# Front_DisplayKey.net
KiCad netlist of a schematic drawn in Altium Designer
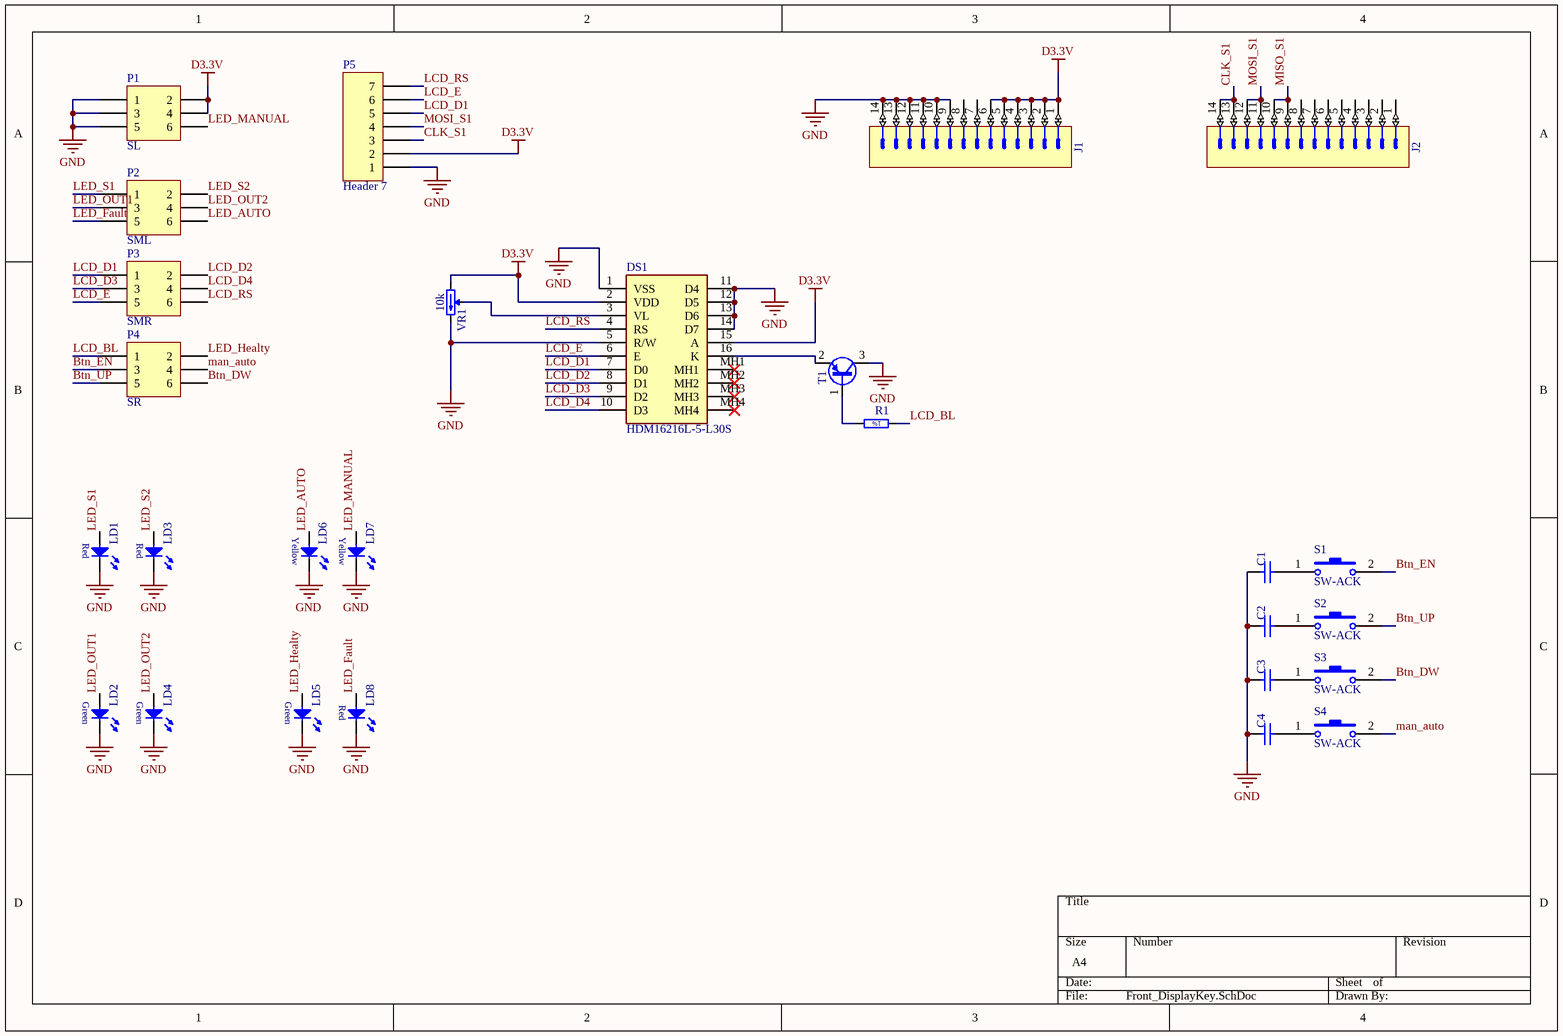
[diagram p0: Front_DisplayKey.SchDoc]

(export (version "E")
  (design (tool "Eeschema 10.0.6"))
  (components
    (comp (ref "C1")
      (value "0.1uf")
      (footprint "CAPC2012X135N")
      (description "0092-0004-8")
      (fields
        (field (name "PART NUMBER") "CC0805_100NF_50V_10%_X7R")
        (field (name "VOLTAGE") "50V")
        (field (name "AUTHOR") "CERN DEM JLC")
      )
      (libsource (lib "Capacitors") (part "Capacitor - non polarized"))
    )
    (comp (ref "C2")
      (value "0.1uf")
      (footprint "CAPC2012X135N")
      (description "0092-0004-8")
      (fields
        (field (name "PART NUMBER") "CC0805_100NF_50V_10%_X7R")
        (field (name "VOLTAGE") "50V")
        (field (name "AUTHOR") "CERN DEM JLC")
      )
      (libsource (lib "Capacitors") (part "Capacitor - non polarized"))
    )
    (comp (ref "C3")
      (value "0.1uf")
      (footprint "CAPC2012X135N")
      (description "0092-0004-8")
      (fields
        (field (name "PART NUMBER") "CC0805_100NF_50V_10%_X7R")
        (field (name "VOLTAGE") "50V")
        (field (name "AUTHOR") "CERN DEM JLC")
      )
      (libsource (lib "Capacitors") (part "Capacitor - non polarized"))
    )
    (comp (ref "C4")
      (value "0.1uf")
      (footprint "CAPC2012X135N")
      (description "0092-0004-8")
      (fields
        (field (name "PART NUMBER") "CC0805_100NF_50V_10%_X7R")
        (field (name "VOLTAGE") "50V")
        (field (name "AUTHOR") "CERN DEM JLC")
      )
      (libsource (lib "Capacitors") (part "Capacitor - non polarized"))
    )
    (comp (ref "DS1")
      (value "HDM16216L-5-L30S")
      (footprint "SamacSys:HDM16216L5L30S")
      (description "Display")
      (libsource (lib "*") (part "HDM16216L-5-L30S"))
    )
    (comp (ref "J1")
      (value "Header 14")
      (footprint "STELVIO-KONTEK_3910401114400")
      (description "Connector 14 Male")
      (fields
        (field (name "PART NUMBER") "STELVIO-KONTEK_3910401114400")
        (field (name "MANUFACTURER") "STELVIO-KONTEK")
        (field (name "AUTHOR") "CERN DEM JLC")
      )
      (libsource (lib "Connectors") (part "Connector 14 Male"))
    )
    (comp (ref "J2")
      (value "Header 14")
      (footprint "STELVIO-KONTEK_3910401114400")
      (description "Connector 14 Male")
      (fields
        (field (name "PART NUMBER") "STELVIO-KONTEK_3910401114400")
        (field (name "MANUFACTURER") "STELVIO-KONTEK")
        (field (name "AUTHOR") "CERN DEM JLC")
      )
      (libsource (lib "Connectors") (part "Connector 14 Male"))
    )
    (comp (ref "LD1")
      (value "Red")
      (footprint "LED_5MM_RED_1C-2A")
      (description "LED Red 1C 2A")
      (fields
        (field (name "PART NUMBER") "LED_AVAGO_HLMP-3301")
        (field (name "MANUFACTURER") "AVAGO TECHNOLOGIES")
        (field (name "AUTHOR") "CERN DEM JLC")
      )
      (libsource (lib "ICs And Semiconductors") (part "LED Red 1C 2A"))
    )
    (comp (ref "LD2")
      (value "Green")
      (footprint "LED_3MM_GREEN_1C-2A")
      (description "LED Green 1C 2A")
      (fields
        (field (name "PART NUMBER") "LED_AVAGO_HLMP-1790")
        (field (name "MANUFACTURER") "AVAGO TECHNOLOGIES")
        (field (name "AUTHOR") "CERN DEM JLC")
      )
      (libsource (lib "ICs And Semiconductors") (part "LED Green 1C 2A"))
    )
    (comp (ref "LD3")
      (value "Red")
      (footprint "LED_5MM_RED_1C-2A")
      (description "LED Red 1C 2A")
      (fields
        (field (name "PART NUMBER") "LED_AVAGO_HLMP-3301")
        (field (name "MANUFACTURER") "AVAGO TECHNOLOGIES")
        (field (name "AUTHOR") "CERN DEM JLC")
      )
      (libsource (lib "ICs And Semiconductors") (part "LED Red 1C 2A"))
    )
    (comp (ref "LD4")
      (value "Green")
      (footprint "LED_3MM_GREEN_1C-2A")
      (description "LED Green 1C 2A")
      (fields
        (field (name "PART NUMBER") "LED_AVAGO_HLMP-1790")
        (field (name "MANUFACTURER") "AVAGO TECHNOLOGIES")
        (field (name "AUTHOR") "CERN DEM JLC")
      )
      (libsource (lib "ICs And Semiconductors") (part "LED Green 1C 2A"))
    )
    (comp (ref "LD5")
      (value "Green")
      (footprint "LED_3MM_GREEN_1C-2A")
      (description "LED Green 1C 2A")
      (fields
        (field (name "PART NUMBER") "LED_AVAGO_HLMP-1790")
        (field (name "MANUFACTURER") "AVAGO TECHNOLOGIES")
        (field (name "AUTHOR") "CERN DEM JLC")
      )
      (libsource (lib "ICs And Semiconductors") (part "LED Green 1C 2A"))
    )
    (comp (ref "LD6")
      (value "Yellow")
      (footprint "LED_3MM_YELLOW_1C-2A")
      (description "LED Yellow 1C 2A")
      (fields
        (field (name "PART NUMBER") "LED_AVAGO_HLMP-1719")
        (field (name "MANUFACTURER") "AVAGO TECHNOLOGIES")
        (field (name "AUTHOR") "CERN DEM JLC")
      )
      (libsource (lib "ICs And Semiconductors") (part "LED Yellow 1C 2A"))
    )
    (comp (ref "LD7")
      (value "Yellow")
      (footprint "LED_3MM_YELLOW_1C-2A")
      (description "LED Yellow 1C 2A")
      (fields
        (field (name "PART NUMBER") "LED_AVAGO_HLMP-1719")
        (field (name "MANUFACTURER") "AVAGO TECHNOLOGIES")
        (field (name "AUTHOR") "CERN DEM JLC")
      )
      (libsource (lib "ICs And Semiconductors") (part "LED Yellow 1C 2A"))
    )
    (comp (ref "LD8")
      (value "Red")
      (footprint "LED_5MM_RED_1C-2A")
      (description "LED Red 1C 2A")
      (fields
        (field (name "PART NUMBER") "LED_AVAGO_HLMP-3301")
        (field (name "MANUFACTURER") "AVAGO TECHNOLOGIES")
        (field (name "AUTHOR") "CERN DEM JLC")
      )
      (libsource (lib "ICs And Semiconductors") (part "LED Red 1C 2A"))
    )
    (comp (ref "P1")
      (value "SL")
      (footprint "HDR2X3")
      (description "Header, 3-Pin, Dual row")
      (fields (field (name "PUBLISHER") "Altium Limited"))
      (libsource (lib "Miscellaneous Connectors") (part "Header 3X2"))
    )
    (comp (ref "P2")
      (value "SML")
      (footprint "HDR2X3")
      (description "Header, 3-Pin, Dual row")
      (fields (field (name "PUBLISHER") "Altium Limited"))
      (libsource (lib "Miscellaneous Connectors") (part "Header 3X2"))
    )
    (comp (ref "P3")
      (value "SMR")
      (footprint "HDR2X3")
      (description "Header, 3-Pin, Dual row")
      (fields (field (name "PUBLISHER") "Altium Limited"))
      (libsource (lib "Miscellaneous Connectors") (part "Header 3X2"))
    )
    (comp (ref "P4")
      (value "SR")
      (footprint "HDR2X3")
      (description "Header, 3-Pin, Dual row")
      (fields (field (name "PUBLISHER") "Altium Limited"))
      (libsource (lib "Miscellaneous Connectors") (part "Header 3X2"))
    )
    (comp (ref "P5")
      (value "Header 7")
      (footprint "HDR1X7")
      (description "Header, 7-Pin")
      (fields (field (name "PUBLISHER") "Altium Limited"))
      (libsource (lib "Miscellaneous Connectors") (part "Header 7"))
    )
    (comp (ref "R1")
      (value "1k")
      (footprint "RESC2012X60N")
      (description "Resistor - 1%")
      (fields
        (field (name "PART NUMBER") "R0805_1K_1%_0.125W_100PPM")
        (field (name "POWER") "0.125W")
        (field (name "AUTHOR") "CERN DEM JLC")
      )
      (libsource (lib "Resistors") (part "Resistor - 1%"))
    )
    (comp (ref "S1")
      (value "SW-ACK")
      (footprint "SW_PB1")
      (description "Switch")
      (fields (field (name "PUBLISHER") "Altium Limited"))
      (libsource (lib "Miscellaneous Devices") (part "SW-PB"))
    )
    (comp (ref "S2")
      (value "SW-ACK")
      (footprint "SW_PB1")
      (description "Switch")
      (fields (field (name "PUBLISHER") "Altium Limited"))
      (libsource (lib "Miscellaneous Devices") (part "SW-PB"))
    )
    (comp (ref "S3")
      (value "SW-ACK")
      (footprint "SW_PB1")
      (description "Switch")
      (fields (field (name "PUBLISHER") "Altium Limited"))
      (libsource (lib "Miscellaneous Devices") (part "SW-PB"))
    )
    (comp (ref "S4")
      (value "SW-ACK")
      (footprint "SW_PB1")
      (description "Switch")
      (fields (field (name "PUBLISHER") "Altium Limited"))
      (libsource (lib "Miscellaneous Devices") (part "SW-PB"))
    )
    (comp (ref "T1")
      (value "MMBT3906LT1G")
      (footprint "SOT95P240X110-3N")
      (description "0235-0223-4")
      (fields
        (field (name "PART NUMBER") "BSR18A")
        (field (name "MANUFACTURER") "FAIRCHILD SEMICONDUCTOR")
        (field (name "AUTHOR") "CERN DEM JLC")
      )
      (libsource (lib "ICs And Semiconductors") (part "PNP B1 E2 C3"))
    )
    (comp (ref "VR1")
      (value "10k")
      (footprint "VR5")
      (description "0141-0259-5")
      (fields
        (field (name "PART NUMBER") "TRIM_12T_100K_BOURNS_3266W-1-104LF")
        (field (name "POWER") "0.25W")
        (field (name "AUTHOR") "CERN DEM JLC")
      )
      (libsource (lib "Resistors") (part "Trimming Potentiometer"))
    )
  )
  (nets
    (net (code "1") (name "/Btn_DW") (class "Default")
      (node (ref "P4") (pin "6") (pinfunction "6_6") (pintype "passive"))
      (node (ref "S3") (pin "2") (pinfunction "2_2") (pintype "passive"))
    )
    (net (code "2") (name "/Btn_EN") (class "Default")
      (node (ref "P4") (pin "3") (pinfunction "3_3") (pintype "passive"))
      (node (ref "S1") (pin "2") (pinfunction "2_2") (pintype "passive"))
    )
    (net (code "3") (name "/Btn_UP") (class "Default")
      (node (ref "P4") (pin "5") (pinfunction "5_5") (pintype "passive"))
      (node (ref "S2") (pin "2") (pinfunction "2_2") (pintype "passive"))
    )
    (net (code "4") (name "/CLK_S1") (class "Default")
      (node (ref "J2") (pin "13") (pinfunction "13_13") (pintype "bidirectional"))
      (node (ref "J2") (pin "14") (pinfunction "14_14") (pintype "bidirectional"))
      (node (ref "P5") (pin "3") (pinfunction "3_3") (pintype "passive"))
    )
    (net (code "5") (name "/LCD_BL") (class "Default")
      (node (ref "P4") (pin "1") (pinfunction "1_1") (pintype "passive"))
      (node (ref "R1") (pin "1") (pinfunction "1_1") (pintype "passive"))
    )
    (net (code "6") (name "/LCD_D1") (class "Default")
      (node (ref "DS1") (pin "7") (pinfunction "D0_7") (pintype "passive"))
      (node (ref "P3") (pin "1") (pinfunction "1_1") (pintype "passive"))
      (node (ref "P5") (pin "5") (pinfunction "5_5") (pintype "passive"))
    )
    (net (code "7") (name "/LCD_D2") (class "Default")
      (node (ref "DS1") (pin "8") (pinfunction "D1_8") (pintype "passive"))
      (node (ref "P3") (pin "2") (pinfunction "2_2") (pintype "passive"))
    )
    (net (code "8") (name "/LCD_D3") (class "Default")
      (node (ref "DS1") (pin "9") (pinfunction "D2_9") (pintype "passive"))
      (node (ref "P3") (pin "3") (pinfunction "3_3") (pintype "passive"))
    )
    (net (code "9") (name "/LCD_D4") (class "Default")
      (node (ref "DS1") (pin "10") (pinfunction "D3_10") (pintype "passive"))
      (node (ref "P3") (pin "4") (pinfunction "4_4") (pintype "passive"))
    )
    (net (code "10") (name "/LCD_E") (class "Default")
      (node (ref "DS1") (pin "6") (pinfunction "E_6") (pintype "passive"))
      (node (ref "P3") (pin "5") (pinfunction "5_5") (pintype "passive"))
      (node (ref "P5") (pin "6") (pinfunction "6_6") (pintype "passive"))
    )
    (net (code "11") (name "/LCD_RS") (class "Default")
      (node (ref "DS1") (pin "4") (pinfunction "RS_4") (pintype "passive"))
      (node (ref "P3") (pin "6") (pinfunction "6_6") (pintype "passive"))
      (node (ref "P5") (pin "7") (pinfunction "7_7") (pintype "passive"))
    )
    (net (code "12") (name "/LED_AUTO") (class "Default")
      (node (ref "LD6") (pin "2") (pinfunction "A_2") (pintype "passive"))
      (node (ref "P2") (pin "6") (pinfunction "6_6") (pintype "passive"))
    )
    (net (code "13") (name "/LED_Fault") (class "Default")
      (node (ref "LD8") (pin "2") (pinfunction "A_2") (pintype "passive"))
      (node (ref "P2") (pin "5") (pinfunction "5_5") (pintype "passive"))
    )
    (net (code "14") (name "/LED_Healty") (class "Default")
      (node (ref "LD5") (pin "2") (pinfunction "A_2") (pintype "passive"))
      (node (ref "P4") (pin "2") (pinfunction "2_2") (pintype "passive"))
    )
    (net (code "15") (name "/LED_MANUAL") (class "Default")
      (node (ref "LD7") (pin "2") (pinfunction "A_2") (pintype "passive"))
      (node (ref "P1") (pin "6") (pinfunction "6_6") (pintype "passive"))
    )
    (net (code "16") (name "/LED_OUT1") (class "Default")
      (node (ref "LD2") (pin "2") (pinfunction "A_2") (pintype "passive"))
      (node (ref "P2") (pin "3") (pinfunction "3_3") (pintype "passive"))
    )
    (net (code "17") (name "/LED_OUT2") (class "Default")
      (node (ref "LD4") (pin "2") (pinfunction "A_2") (pintype "passive"))
      (node (ref "P2") (pin "4") (pinfunction "4_4") (pintype "passive"))
    )
    (net (code "18") (name "/LED_S1") (class "Default")
      (node (ref "LD1") (pin "2") (pinfunction "A_2") (pintype "passive"))
      (node (ref "P2") (pin "1") (pinfunction "1_1") (pintype "passive"))
    )
    (net (code "19") (name "/LED_S2") (class "Default")
      (node (ref "LD3") (pin "2") (pinfunction "A_2") (pintype "passive"))
      (node (ref "P2") (pin "2") (pinfunction "2_2") (pintype "passive"))
    )
    (net (code "20") (name "/MISO_S1") (class "Default")
      (node (ref "J2") (pin "10") (pinfunction "10_10") (pintype "bidirectional"))
      (node (ref "J2") (pin "9") (pinfunction "9_9") (pintype "bidirectional"))
    )
    (net (code "21") (name "/MOSI_S1") (class "Default")
      (node (ref "J2") (pin "11") (pinfunction "11_11") (pintype "bidirectional"))
      (node (ref "J2") (pin "12") (pinfunction "12_12") (pintype "bidirectional"))
      (node (ref "P5") (pin "4") (pinfunction "4_4") (pintype "passive"))
    )
    (net (code "22") (name "/man_auto") (class "Default")
      (node (ref "P4") (pin "4") (pinfunction "4_4") (pintype "passive"))
      (node (ref "S4") (pin "2") (pinfunction "2_2") (pintype "passive"))
    )
    (net (code "23") (name "D3.3V") (class "Default")
      (node (ref "DS1") (pin "15") (pinfunction "A_15") (pintype "passive"))
      (node (ref "DS1") (pin "2") (pinfunction "VDD_2") (pintype "passive"))
      (node (ref "J1") (pin "1") (pinfunction "1_1") (pintype "bidirectional"))
      (node (ref "J1") (pin "2") (pinfunction "2_2") (pintype "bidirectional"))
      (node (ref "J1") (pin "3") (pinfunction "3_3") (pintype "bidirectional"))
      (node (ref "J1") (pin "4") (pinfunction "4_4") (pintype "bidirectional"))
      (node (ref "J1") (pin "5") (pinfunction "5_5") (pintype "bidirectional"))
      (node (ref "J1") (pin "6") (pinfunction "6_6") (pintype "bidirectional"))
      (node (ref "P1") (pin "2") (pinfunction "2_2") (pintype "passive"))
      (node (ref "P1") (pin "4") (pinfunction "4_4") (pintype "passive"))
      (node (ref "P5") (pin "2") (pinfunction "2_2") (pintype "passive"))
      (node (ref "VR1") (pin "1") (pinfunction "CCW_1") (pintype "passive"))
    )
    (net (code "24") (name "GND") (class "Default")
      (node (ref "C1") (pin "1") (pinfunction "1_1") (pintype "passive"))
      (node (ref "C2") (pin "1") (pinfunction "1_1") (pintype "passive"))
      (node (ref "C3") (pin "1") (pinfunction "1_1") (pintype "passive"))
      (node (ref "C4") (pin "1") (pinfunction "1_1") (pintype "passive"))
      (node (ref "DS1") (pin "1") (pinfunction "VSS_1") (pintype "passive"))
      (node (ref "DS1") (pin "11") (pinfunction "D4_11") (pintype "passive"))
      (node (ref "DS1") (pin "12") (pinfunction "D5_12") (pintype "passive"))
      (node (ref "DS1") (pin "13") (pinfunction "D6_13") (pintype "passive"))
      (node (ref "DS1") (pin "14") (pinfunction "D7_14") (pintype "passive"))
      (node (ref "DS1") (pin "5") (pinfunction "R/W_5") (pintype "passive"))
      (node (ref "J1") (pin "10") (pinfunction "10_10") (pintype "bidirectional"))
      (node (ref "J1") (pin "11") (pinfunction "11_11") (pintype "bidirectional"))
      (node (ref "J1") (pin "12") (pinfunction "12_12") (pintype "bidirectional"))
      (node (ref "J1") (pin "13") (pinfunction "13_13") (pintype "bidirectional"))
      (node (ref "J1") (pin "14") (pinfunction "14_14") (pintype "bidirectional"))
      (node (ref "J1") (pin "9") (pinfunction "9_9") (pintype "bidirectional"))
      (node (ref "LD1") (pin "1") (pinfunction "C_1") (pintype "passive"))
      (node (ref "LD2") (pin "1") (pinfunction "C_1") (pintype "passive"))
      (node (ref "LD3") (pin "1") (pinfunction "C_1") (pintype "passive"))
      (node (ref "LD4") (pin "1") (pinfunction "C_1") (pintype "passive"))
      (node (ref "LD5") (pin "1") (pinfunction "C_1") (pintype "passive"))
      (node (ref "LD6") (pin "1") (pinfunction "C_1") (pintype "passive"))
      (node (ref "LD7") (pin "1") (pinfunction "C_1") (pintype "passive"))
      (node (ref "LD8") (pin "1") (pinfunction "C_1") (pintype "passive"))
      (node (ref "P1") (pin "1") (pinfunction "1_1") (pintype "passive"))
      (node (ref "P1") (pin "3") (pinfunction "3_3") (pintype "passive"))
      (node (ref "P1") (pin "5") (pinfunction "5_5") (pintype "passive"))
      (node (ref "P5") (pin "1") (pinfunction "1_1") (pintype "passive"))
      (node (ref "T1") (pin "3") (pinfunction "C_3") (pintype "passive"))
      (node (ref "VR1") (pin "3") (pinfunction "CW_3") (pintype "passive"))
    )
    (net (code "25") (name "Net-(C1-Pad2)") (class "Default")
      (node (ref "C1") (pin "2") (pinfunction "2_2") (pintype "passive"))
      (node (ref "S1") (pin "1") (pinfunction "1_1") (pintype "passive"))
    )
    (net (code "26") (name "Net-(C2-Pad2)") (class "Default")
      (node (ref "C2") (pin "2") (pinfunction "2_2") (pintype "passive"))
      (node (ref "S2") (pin "1") (pinfunction "1_1") (pintype "passive"))
    )
    (net (code "27") (name "Net-(C3-Pad2)") (class "Default")
      (node (ref "C3") (pin "2") (pinfunction "2_2") (pintype "passive"))
      (node (ref "S3") (pin "1") (pinfunction "1_1") (pintype "passive"))
    )
    (net (code "28") (name "Net-(C4-Pad2)") (class "Default")
      (node (ref "C4") (pin "2") (pinfunction "2_2") (pintype "passive"))
      (node (ref "S4") (pin "1") (pinfunction "1_1") (pintype "passive"))
    )
    (net (code "29") (name "Net-(DS1-K)") (class "Default")
      (node (ref "DS1") (pin "16") (pinfunction "K_16") (pintype "passive"))
      (node (ref "T1") (pin "2") (pinfunction "E_2") (pintype "passive"))
    )
    (net (code "30") (name "Net-(DS1-VL)") (class "Default")
      (node (ref "DS1") (pin "3") (pinfunction "VL_3") (pintype "passive"))
      (node (ref "VR1") (pin "2") (pinfunction "W_2") (pintype "passive"))
    )
    (net (code "31") (name "Net-(T1-B)") (class "Default")
      (node (ref "R1") (pin "2") (pinfunction "2_2") (pintype "passive"))
      (node (ref "T1") (pin "1") (pinfunction "B_1") (pintype "passive"))
    )
    (net (code "32") (name "unconnected-(DS1-PadMH1)") (class "Default")
      (node (ref "DS1") (pin "MH1") (pinfunction "MH1_MH1") (pintype "passive+no_connect"))
    )
    (net (code "33") (name "unconnected-(DS1-PadMH2)") (class "Default")
      (node (ref "DS1") (pin "MH2") (pinfunction "MH2_MH2") (pintype "passive+no_connect"))
    )
    (net (code "34") (name "unconnected-(DS1-PadMH3)") (class "Default")
      (node (ref "DS1") (pin "MH3") (pinfunction "MH3_MH3") (pintype "passive+no_connect"))
    )
    (net (code "35") (name "unconnected-(DS1-PadMH4)") (class "Default")
      (node (ref "DS1") (pin "MH4") (pinfunction "MH4_MH4") (pintype "passive+no_connect"))
    )
    (net (code "36") (name "unconnected-(J1-Pad7)") (class "Default")
      (node (ref "J1") (pin "7") (pinfunction "7_7") (pintype "bidirectional"))
    )
    (net (code "37") (name "unconnected-(J1-Pad8)") (class "Default")
      (node (ref "J1") (pin "8") (pinfunction "8_8") (pintype "bidirectional"))
    )
    (net (code "38") (name "unconnected-(J2-Pad1)") (class "Default")
      (node (ref "J2") (pin "1") (pinfunction "1_1") (pintype "bidirectional"))
    )
    (net (code "39") (name "unconnected-(J2-Pad2)") (class "Default")
      (node (ref "J2") (pin "2") (pinfunction "2_2") (pintype "bidirectional"))
    )
    (net (code "40") (name "unconnected-(J2-Pad3)") (class "Default")
      (node (ref "J2") (pin "3") (pinfunction "3_3") (pintype "bidirectional"))
    )
    (net (code "41") (name "unconnected-(J2-Pad4)") (class "Default")
      (node (ref "J2") (pin "4") (pinfunction "4_4") (pintype "bidirectional"))
    )
    (net (code "42") (name "unconnected-(J2-Pad5)") (class "Default")
      (node (ref "J2") (pin "5") (pinfunction "5_5") (pintype "bidirectional"))
    )
    (net (code "43") (name "unconnected-(J2-Pad6)") (class "Default")
      (node (ref "J2") (pin "6") (pinfunction "6_6") (pintype "bidirectional"))
    )
    (net (code "44") (name "unconnected-(J2-Pad7)") (class "Default")
      (node (ref "J2") (pin "7") (pinfunction "7_7") (pintype "bidirectional"))
    )
    (net (code "45") (name "unconnected-(J2-Pad8)") (class "Default")
      (node (ref "J2") (pin "8") (pinfunction "8_8") (pintype "bidirectional"))
    )
  )
)
